# char.net
KiCad netlist of a schematic drawn in EAGLE
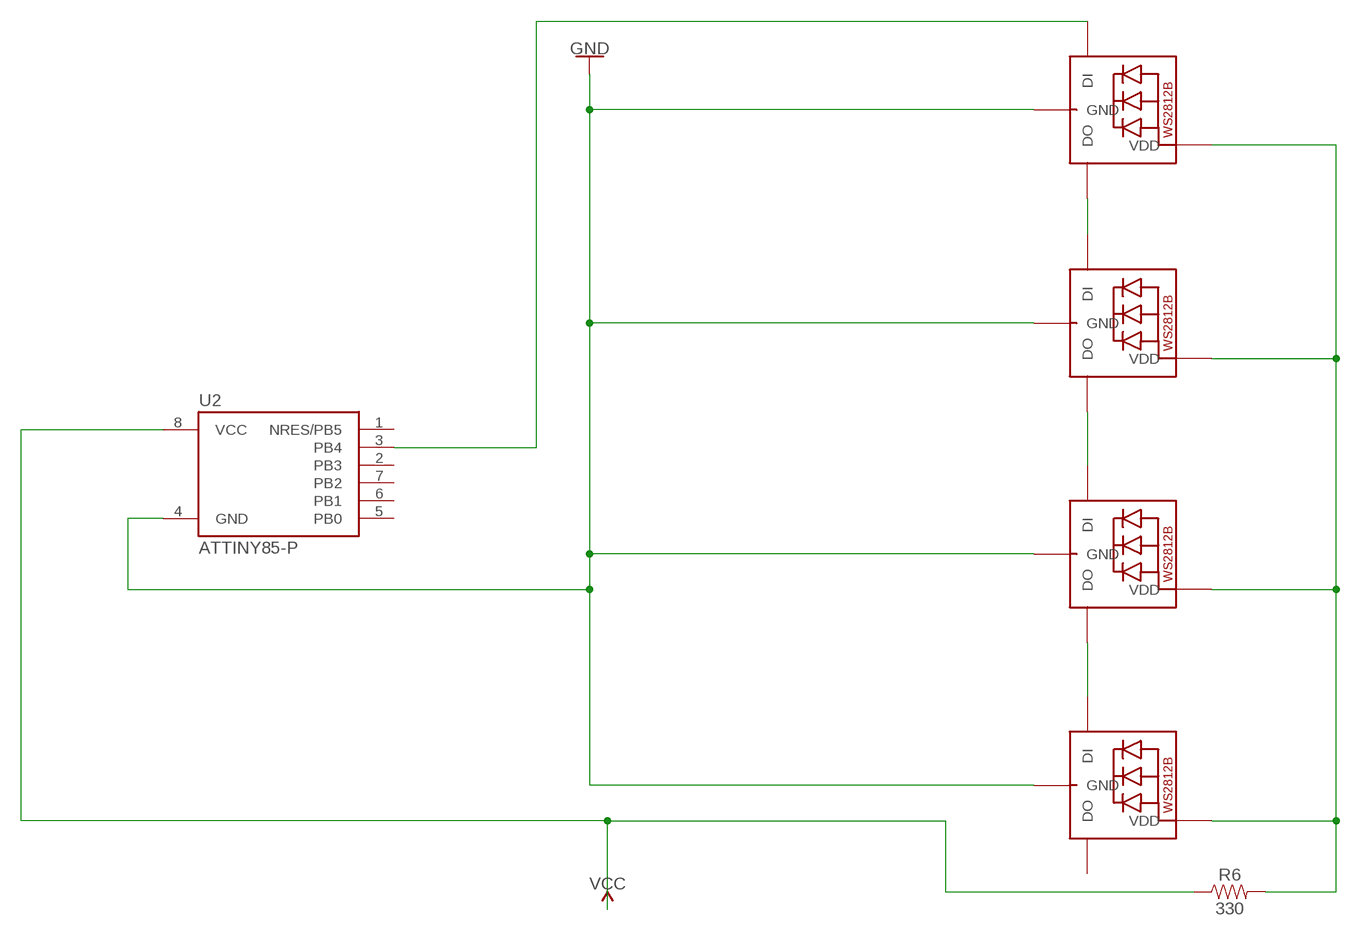
[diagram p0: schematic, sheet 1]

(export (version "E")
  (design (tool "Eeschema 10.0.6"))
  (components
    (comp (ref "R6")
      (value "330")
      (footprint "eagle-import:AXIAL-0.3")
      (libsource (lib "eagle-import") (part "330OHM-HORIZ-1/10W-5%"))
    )
    (comp (ref "U$1")
      (value "THROHOLE")
      (footprint "eagle-import:LED5MMRGB")
      (libsource (lib "eagle-import") (part "THROHOLE"))
    )
    (comp (ref "U$2")
      (value "THROHOLE")
      (footprint "eagle-import:LED5MMRGB")
      (libsource (lib "eagle-import") (part "THROHOLE"))
    )
    (comp (ref "U$3")
      (value "THROHOLE")
      (footprint "eagle-import:LED5MMRGB")
      (libsource (lib "eagle-import") (part "THROHOLE"))
    )
    (comp (ref "U$4")
      (value "THROHOLE")
      (footprint "eagle-import:LED5MMRGB")
      (libsource (lib "eagle-import") (part "THROHOLE"))
    )
    (comp (ref "U2")
      (value "ATTINY85-P")
      (footprint "eagle-import:PDIP08_300MIL")
      (libsource (lib "eagle-import") (part "ATTINY85P-"))
    )
  )
  (nets
    (net (code "1") (name "GND") (class "Default")
      (node (ref "U$1") (pin "2") (pinfunction "GND_2") (pintype "power_in"))
      (node (ref "U$2") (pin "2") (pinfunction "GND_2") (pintype "power_in"))
      (node (ref "U$3") (pin "2") (pinfunction "GND_2") (pintype "power_in"))
      (node (ref "U$4") (pin "2") (pinfunction "GND_2") (pintype "power_in"))
      (node (ref "U2") (pin "4") (pinfunction "GND_4") (pintype "power_in"))
    )
    (net (code "2") (name "Net-(R6-2)") (class "Default")
      (node (ref "R6") (pin "P$2") (pinfunction "2_P$2") (pintype "passive"))
      (node (ref "U$1") (pin "3") (pinfunction "VDD_3") (pintype "power_in"))
      (node (ref "U$2") (pin "3") (pinfunction "VDD_3") (pintype "power_in"))
      (node (ref "U$3") (pin "3") (pinfunction "VDD_3") (pintype "power_in"))
      (node (ref "U$4") (pin "3") (pinfunction "VDD_3") (pintype "power_in"))
    )
    (net (code "3") (name "Net-(U$1-DI)") (class "Default")
      (node (ref "U$1") (pin "1") (pinfunction "DI_1") (pintype "input"))
      (node (ref "U$4") (pin "4") (pinfunction "DO_4") (pintype "output"))
    )
    (net (code "4") (name "Net-(U$1-DO)") (class "Default")
      (node (ref "U$1") (pin "4") (pinfunction "DO_4") (pintype "output"))
      (node (ref "U$2") (pin "1") (pinfunction "DI_1") (pintype "input"))
    )
    (net (code "5") (name "Net-(U$2-DO)") (class "Default")
      (node (ref "U$2") (pin "4") (pinfunction "DO_4") (pintype "output"))
      (node (ref "U$3") (pin "1") (pinfunction "DI_1") (pintype "input"))
    )
    (net (code "6") (name "Net-(U$4-DI)") (class "Default")
      (node (ref "U$4") (pin "1") (pinfunction "DI_1") (pintype "input"))
      (node (ref "U2") (pin "3") (pinfunction "PB4_3") (pintype "bidirectional"))
    )
    (net (code "7") (name "VCC") (class "Default")
      (node (ref "R6") (pin "P$1") (pinfunction "1_P$1") (pintype "passive"))
      (node (ref "U2") (pin "8") (pinfunction "VCC_8") (pintype "power_in"))
    )
    (net (code "8") (name "unconnected-(U$3-DO-Pad4)") (class "Default")
      (node (ref "U$3") (pin "4") (pinfunction "DO_4") (pintype "output"))
    )
    (net (code "9") (name "unconnected-(U2-NRES{slash}PB5-Pad1)") (class "Default")
      (node (ref "U2") (pin "1") (pinfunction "NRES/PB5_1") (pintype "bidirectional"))
    )
    (net (code "10") (name "unconnected-(U2-PB0-Pad5)") (class "Default")
      (node (ref "U2") (pin "5") (pinfunction "PB0_5") (pintype "bidirectional"))
    )
    (net (code "11") (name "unconnected-(U2-PB1-Pad6)") (class "Default")
      (node (ref "U2") (pin "6") (pinfunction "PB1_6") (pintype "bidirectional"))
    )
    (net (code "12") (name "unconnected-(U2-PB2-Pad7)") (class "Default")
      (node (ref "U2") (pin "7") (pinfunction "PB2_7") (pintype "bidirectional"))
    )
    (net (code "13") (name "unconnected-(U2-PB3-Pad2)") (class "Default")
      (node (ref "U2") (pin "2") (pinfunction "PB3_2") (pintype "bidirectional"))
    )
  )
)
